# sd_accel.net
KiCad netlist of a schematic drawn in Altium Designer
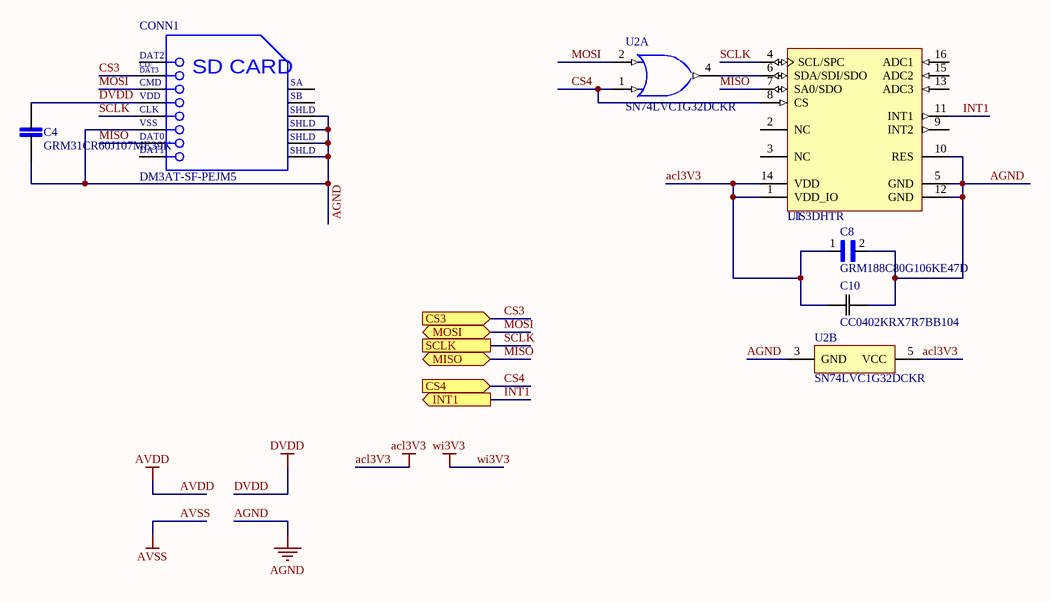
[diagram p0: sd_accel.SchDoc]

(export (version "E")
  (design (tool "Eeschema 10.0.6"))
  (components
    (comp (ref "C4")
      (value "GRM31CR60J107ME39K")
      (footprint "*CAPC3216X190")
      (description "MURATA - GRM31CR60J107ME39K - COND, 100µF, 6.3V, 20%, X5R, 1206")
      (fields (field (name "TOLERANCE") "20%") (field (name "VOLTAGE") "6.3V"))
      (libsource (lib "EE_smallOB_BW_v1.0") (part "GRM31CR60J107ME39K"))
    )
    (comp (ref "C8")
      (value "GRM188C80G106KE47D")
      (footprint "*CAPC1608X90N")
      (description "CAP CER 10UF 4V X6S 0603")
      (fields (field (name "TOLERANCE") "10%"))
      (libsource (lib "EE_smallOB_BW_v1.0") (part "GRM188C80G106KE47D"))
    )
    (comp (ref "C10")
      (value "CC0402KRX7R7BB104")
      (footprint "YAG_CC0402")
      (description "CAP CER 0.1UF 16V X7R 0402")
      (fields (field (name "TOLERANCE") "10%") (field (name "VOLTAGE") "16V"))
      (libsource (lib "EE_smallOB_BW_v1.0") (part "CC0402KRX7R7BB104"))
    )
    (comp (ref "CONN1")
      (value "DM3AT-SF-PEJM5")
      (footprint "HRS-DM3AT-8_V")
      (description "CONN MICRO SD CARD PUSH-PUSH R/A")
      (libsource (lib "EE_smallOB_BW_v1.0") (part "DM3AT-SF-PEJM5"))
    )
    (comp (ref "U1")
      (value "LIS3DHTR")
      (footprint "STM-LGA-16")
      (description "ACCEL 2-16G I2C/SPI 16LGA")
      (libsource (lib "EE_smallOB_BW_v1.0") (part "LIS3DHTR"))
    )
    (comp (ref "U2")
      (value "SN74LVC1G32DCKR")
      (footprint "DCK0005A_N")
      (description "IC GATE OR 1CH 2-INP SC70-5")
      (libsource (lib "EE_smallOB_BW_v1.0") (part "SN74LVC1G32DCKR"))
    )
  )
  (nets
    (net (code "1") (name "/CS3") (class "Default")
      (node (ref "CONN1") (pin "2") (pinfunction "CD/DAT3_2") (pintype "passive"))
    )
    (net (code "2") (name "/CS4") (class "Default")
      (node (ref "U1") (pin "8") (pinfunction "CS_8") (pintype "input"))
      (node (ref "U2") (pin "1") (pinfunction "A_1") (pintype "input"))
    )
    (net (code "3") (name "/INT1") (class "Default")
      (node (ref "U1") (pin "11") (pinfunction "INT1_11") (pintype "output"))
    )
    (net (code "4") (name "/MISO") (class "Default")
      (node (ref "CONN1") (pin "7") (pinfunction "DAT0_7") (pintype "passive"))
      (node (ref "U1") (pin "7") (pinfunction "SA0/SDO_7") (pintype "bidirectional"))
    )
    (net (code "5") (name "/MOSI") (class "Default")
      (node (ref "CONN1") (pin "3") (pinfunction "CMD_3") (pintype "passive"))
      (node (ref "U2") (pin "2") (pinfunction "B_2") (pintype "input"))
    )
    (net (code "6") (name "/SCLK") (class "Default")
      (node (ref "CONN1") (pin "5") (pinfunction "CLK_5") (pintype "passive"))
      (node (ref "U1") (pin "4") (pinfunction "SCL/SPC_4") (pintype "bidirectional"))
    )
    (net (code "7") (name "AGND") (class "Default")
      (node (ref "C10") (pin "2") (pinfunction "2_2") (pintype "passive"))
      (node (ref "C4") (pin "2") (pinfunction "2_2") (pintype "passive"))
      (node (ref "C8") (pin "2") (pinfunction "2_2") (pintype "passive"))
      (node (ref "CONN1") (pin "11") (pinfunction "SHLD_11") (pintype "passive"))
      (node (ref "CONN1") (pin "12") (pinfunction "SHLD_12") (pintype "passive"))
      (node (ref "CONN1") (pin "13") (pinfunction "SHLD_13") (pintype "passive"))
      (node (ref "CONN1") (pin "14") (pinfunction "SHLD_14") (pintype "passive"))
      (node (ref "CONN1") (pin "6") (pinfunction "VSS_6") (pintype "passive"))
      (node (ref "U1") (pin "10") (pinfunction "RES_10") (pintype "power_in"))
      (node (ref "U1") (pin "12") (pinfunction "GND_12") (pintype "power_in"))
      (node (ref "U1") (pin "5") (pinfunction "GND_5") (pintype "power_in"))
      (node (ref "U2") (pin "3") (pinfunction "GND_3") (pintype "power_in"))
    )
    (net (code "10") (name "DVDD") (class "Default")
      (node (ref "C4") (pin "1") (pinfunction "1_1") (pintype "passive"))
      (node (ref "CONN1") (pin "4") (pinfunction "VDD_4") (pintype "passive"))
    )
    (net (code "11") (name "Net-(U1-SDA{slash}SDI{slash}SDO)") (class "Default")
      (node (ref "U1") (pin "6") (pinfunction "SDA/SDI/SDO_6") (pintype "bidirectional"))
      (node (ref "U2") (pin "4") (pinfunction "Y_4") (pintype "output"))
    )
    (net (code "12") (name "acl3V3") (class "Default")
      (node (ref "C10") (pin "1") (pinfunction "1_1") (pintype "passive"))
      (node (ref "C8") (pin "1") (pinfunction "1_1") (pintype "passive"))
      (node (ref "U1") (pin "1") (pinfunction "VDD_IO_1") (pintype "power_in"))
      (node (ref "U1") (pin "14") (pinfunction "VDD_14") (pintype "power_in"))
      (node (ref "U2") (pin "5") (pinfunction "VCC_5") (pintype "power_in"))
    )
    (net (code "13") (name "unconnected-(CONN1-DAT1-Pad8)") (class "Default")
      (node (ref "CONN1") (pin "8") (pinfunction "DAT1_8") (pintype "passive"))
    )
    (net (code "14") (name "unconnected-(CONN1-DAT2-Pad1)") (class "Default")
      (node (ref "CONN1") (pin "1") (pinfunction "DAT2_1") (pintype "passive"))
    )
    (net (code "15") (name "unconnected-(CONN1-SA-Pad9)") (class "Default")
      (node (ref "CONN1") (pin "9") (pinfunction "SA_9") (pintype "passive"))
    )
    (net (code "16") (name "unconnected-(CONN1-SB-Pad10)") (class "Default")
      (node (ref "CONN1") (pin "10") (pinfunction "SB_10") (pintype "passive"))
    )
    (net (code "17") (name "unconnected-(U1-ADC1-Pad16)") (class "Default")
      (node (ref "U1") (pin "16") (pinfunction "ADC1_16") (pintype "input"))
    )
    (net (code "18") (name "unconnected-(U1-ADC2-Pad15)") (class "Default")
      (node (ref "U1") (pin "15") (pinfunction "ADC2_15") (pintype "input"))
    )
    (net (code "19") (name "unconnected-(U1-ADC3-Pad13)") (class "Default")
      (node (ref "U1") (pin "13") (pinfunction "ADC3_13") (pintype "input"))
    )
    (net (code "20") (name "unconnected-(U1-INT2-Pad9)") (class "Default")
      (node (ref "U1") (pin "9") (pinfunction "INT2_9") (pintype "output"))
    )
    (net (code "21") (name "unconnected-(U1-NC-Pad2)") (class "Default")
      (node (ref "U1") (pin "2") (pinfunction "NC_2") (pintype "passive"))
    )
    (net (code "22") (name "unconnected-(U1-NC-Pad3)") (class "Default")
      (node (ref "U1") (pin "3") (pinfunction "NC_3") (pintype "passive"))
    )
  )
)
